# STM32.net
KiCad netlist of a schematic drawn in Altium Designer
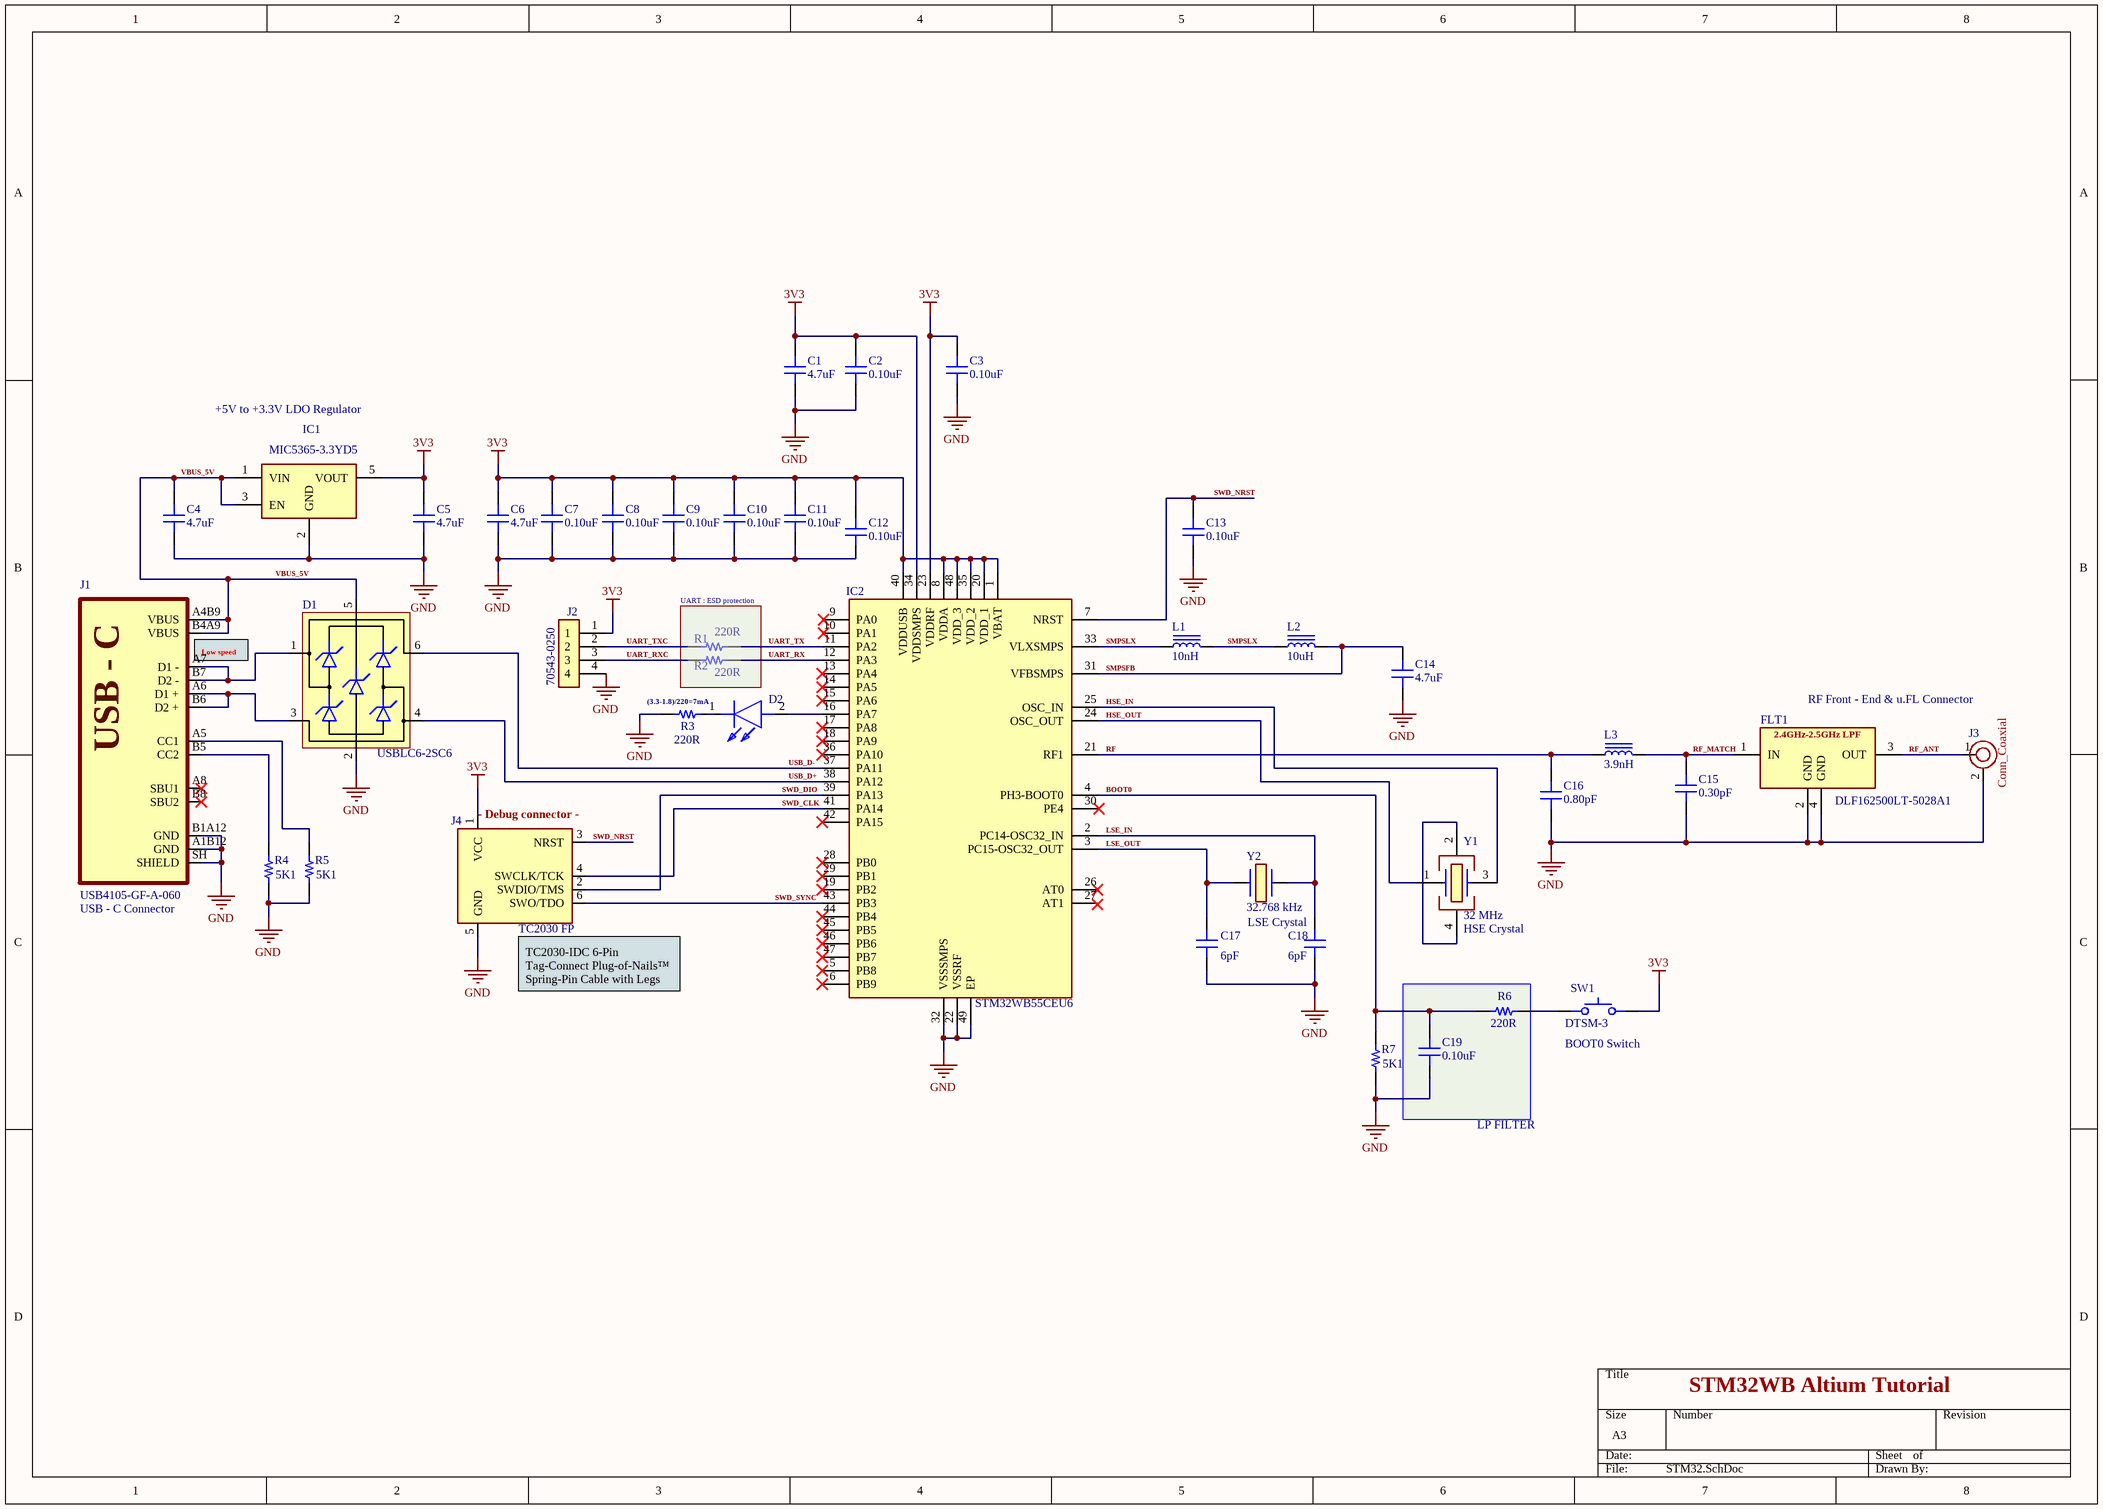
[diagram p0: STM32.SchDoc]

(export (version "E")
  (design (tool "Eeschema 10.0.6"))
  (components
    (comp (ref "C1")
      (value "4.7uF")
      (footprint "CAP 0805/2012")
      (description "CAP CER 4.7UF 10V X7R 0805")
      (fields
        (field (name "PART NUMBER") "CL21B475KPFNNNE")
        (field (name "MANUFACTURER") "Samsung Electro-Mechanics America, Inc.")
      )
      (libsource (lib "Capacitor - Ceramic - Sumsung") (part "CL21B475KPFNNNE"))
    )
    (comp (ref "C2")
      (value "0.10uF")
      (footprint "CAP 0402/1005")
      (description "CAP CER 0.1UF 16V X7R 0402")
      (fields
        (field (name "PART NUMBER") "CL05B104KO5NFNC")
        (field (name "MANUFACTURER") "Samsung Electro-Mechanics America, Inc.")
      )
      (libsource (lib "Capacitor - Ceramic - Sumsung") (part "CL05B104KO5NFNC"))
    )
    (comp (ref "C3")
      (value "0.10uF")
      (footprint "CAP 0402/1005")
      (description "CAP CER 0.1UF 16V X7R 0402")
      (fields
        (field (name "PART NUMBER") "CL05B104KO5NFNC")
        (field (name "MANUFACTURER") "Samsung Electro-Mechanics America, Inc.")
      )
      (libsource (lib "Capacitor - Ceramic - Sumsung") (part "CL05B104KO5NFNC"))
    )
    (comp (ref "C4")
      (value "4.7uF")
      (footprint "CAP 0805/2012")
      (description "CAP CER 4.7UF 10V X7R 0805")
      (fields
        (field (name "PART NUMBER") "CL21B475KPFNNNE")
        (field (name "MANUFACTURER") "Samsung Electro-Mechanics America, Inc.")
      )
      (libsource (lib "Capacitor - Ceramic - Sumsung") (part "CL21B475KPFNNNE"))
    )
    (comp (ref "C5")
      (value "4.7uF")
      (footprint "CAP 0805/2012")
      (description "CAP CER 4.7UF 10V X7R 0805")
      (fields
        (field (name "PART NUMBER") "CL21B475KPFNNNE")
        (field (name "MANUFACTURER") "Samsung Electro-Mechanics America, Inc.")
      )
      (libsource (lib "Capacitor - Ceramic - Sumsung") (part "CL21B475KPFNNNE"))
    )
    (comp (ref "C6")
      (value "4.7uF")
      (footprint "CAP 0805/2012")
      (description "CAP CER 4.7UF 10V X7R 0805")
      (fields
        (field (name "PART NUMBER") "CL21B475KPFNNNE")
        (field (name "MANUFACTURER") "Samsung Electro-Mechanics America, Inc.")
      )
      (libsource (lib "Capacitor - Ceramic - Sumsung") (part "CL21B475KPFNNNE"))
    )
    (comp (ref "C7")
      (value "0.10uF")
      (footprint "CAP 0402/1005")
      (description "CAP CER 0.1UF 16V X7R 0402")
      (fields
        (field (name "PART NUMBER") "CL05B104KO5NFNC")
        (field (name "MANUFACTURER") "Samsung Electro-Mechanics America, Inc.")
      )
      (libsource (lib "Capacitor - Ceramic - Sumsung") (part "CL05B104KO5NFNC"))
    )
    (comp (ref "C8")
      (value "0.10uF")
      (footprint "CAP 0402/1005")
      (description "CAP CER 0.1UF 16V X7R 0402")
      (fields
        (field (name "PART NUMBER") "CL05B104KO5NFNC")
        (field (name "MANUFACTURER") "Samsung Electro-Mechanics America, Inc.")
      )
      (libsource (lib "Capacitor - Ceramic - Sumsung") (part "CL05B104KO5NFNC"))
    )
    (comp (ref "C9")
      (value "0.10uF")
      (footprint "CAP 0402/1005")
      (description "CAP CER 0.1UF 16V X7R 0402")
      (fields
        (field (name "PART NUMBER") "CL05B104KO5NFNC")
        (field (name "MANUFACTURER") "Samsung Electro-Mechanics America, Inc.")
      )
      (libsource (lib "Capacitor - Ceramic - Sumsung") (part "CL05B104KO5NFNC"))
    )
    (comp (ref "C10")
      (value "0.10uF")
      (footprint "CAP 0402/1005")
      (description "CAP CER 0.1UF 16V X7R 0402")
      (fields
        (field (name "PART NUMBER") "CL05B104KO5NFNC")
        (field (name "MANUFACTURER") "Samsung Electro-Mechanics America, Inc.")
      )
      (libsource (lib "Capacitor - Ceramic - Sumsung") (part "CL05B104KO5NFNC"))
    )
    (comp (ref "C11")
      (value "0.10uF")
      (footprint "CAP 0402/1005")
      (description "CAP CER 0.1UF 16V X7R 0402")
      (fields
        (field (name "PART NUMBER") "CL05B104KO5NFNC")
        (field (name "MANUFACTURER") "Samsung Electro-Mechanics America, Inc.")
      )
      (libsource (lib "Capacitor - Ceramic - Sumsung") (part "CL05B104KO5NFNC"))
    )
    (comp (ref "C12")
      (value "0.10uF")
      (footprint "CAP 0402/1005")
      (description "CAP CER 0.1UF 16V X7R 0402")
      (fields
        (field (name "PART NUMBER") "CL05B104KO5NFNC")
        (field (name "MANUFACTURER") "Samsung Electro-Mechanics America, Inc.")
      )
      (libsource (lib "Capacitor - Ceramic - Sumsung") (part "CL05B104KO5NFNC"))
    )
    (comp (ref "C13")
      (value "0.10uF")
      (footprint "CAP 0402/1005")
      (description "CAP CER 0.1UF 16V X7R 0402")
      (fields
        (field (name "PART NUMBER") "CL05B104KO5NFNC")
        (field (name "MANUFACTURER") "Samsung Electro-Mechanics America, Inc.")
      )
      (libsource (lib "Capacitor - Ceramic - Sumsung") (part "CL05B104KO5NFNC"))
    )
    (comp (ref "C14")
      (value "4.7uF")
      (footprint "CAP 0805/2012")
      (description "CAP CER 4.7UF 10V X7R 0805")
      (fields
        (field (name "PART NUMBER") "CL21B475KPFNNNE")
        (field (name "MANUFACTURER") "Samsung Electro-Mechanics America, Inc.")
      )
      (libsource (lib "Capacitor - Ceramic - Sumsung") (part "CL21B475KPFNNNE"))
    )
    (comp (ref "C15")
      (value "0.30pF")
      (footprint "CAP 0201/0603 RF")
      (description "CAP CER 0.3PF 25V NP0 0201")
      (fields
        (field (name "PART NUMBER") "250R05L0R3BV4T")
        (field (name "MANUFACTURER") "Johanson Technology Inc.")
      )
      (libsource (lib "Capacitor - RF") (part "250R05L0R3BV4T"))
    )
    (comp (ref "C16")
      (value "0.80pF")
      (footprint "CAP 0402/1005 RF")
      (description "CAP CER 0.80PF 50V NP0 0402")
      (fields
        (field (name "PART NUMBER") "GJM1555C1HR80BB01D")
        (field (name "MANUFACTURER") "Murata Electronics North America")
      )
      (libsource (lib "Capacitor - RF") (part "GJM1555C1HR80BB01D"))
    )
    (comp (ref "C17")
      (value "6pF")
      (footprint "CAP 0201/0603")
      (description "CAP CER 6PF 25V NP0 0201")
      (fields
        (field (name "PART NUMBER") "CL03C060BA3GNNC")
        (field (name "MANUFACTURER") "Samsung Electro-Mechanics America, Inc.")
      )
      (libsource (lib "Capacitor - Ceramic - Sumsung") (part "CL03C060BA3GNNC"))
    )
    (comp (ref "C18")
      (value "6pF")
      (footprint "CAP 0201/0603")
      (description "CAP CER 6PF 25V NP0 0201")
      (fields
        (field (name "PART NUMBER") "CL03C060BA3GNNC")
        (field (name "MANUFACTURER") "Samsung Electro-Mechanics America, Inc.")
      )
      (libsource (lib "Capacitor - Ceramic - Sumsung") (part "CL03C060BA3GNNC"))
    )
    (comp (ref "C19")
      (value "0.10uF")
      (footprint "CAP 0402/1005")
      (description "CAP CER 0.1UF 16V X7R 0402")
      (fields
        (field (name "PART NUMBER") "CL05B104KO5NFNC")
        (field (name "MANUFACTURER") "Samsung Electro-Mechanics America, Inc.")
      )
      (libsource (lib "Capacitor - Ceramic - Sumsung") (part "CL05B104KO5NFNC"))
    )
    (comp (ref "D1")
      (value "USBLC6-2SC6")
      (footprint "SOT-23-6")
      (description "Low-Capacitance ESD Protection USB")
      (fields (field (name "MANUFACTURER") "STMicroelectronics"))
      (libsource (lib "Own_Library") (part "USBLC6-2SC6"))
    )
    (comp (ref "D2")
      (value "150060GS55040")
      (footprint "LEDC1608X50N")
      (description "LED SMD 0603 Green 520nm")
      (fields (field (name "MOUSER PART NUMBER") "710-150060GS55040"))
      (libsource (lib "Own_Library") (part "150060GS55040"))
    )
    (comp (ref "FLT1")
      (value "DLF162500LT-5028A1")
      (footprint "DLF162500LT5028A1")
      (description "LTCC Low Pass filter 2400-2500MHz")
      (fields (field (name "MOUSER PART NUMBER") "810-DLF16250LT5028A1"))
      (libsource (lib "Own_Library") (part "DLF162500LT-5028A1"))
    )
    (comp (ref "IC1")
      (value "MIC5365-3.3YD5")
      (footprint "SOT95P280X100-5N")
      (description "Integrated Circuit")
      (fields
        (field (name "MANUFACTURER_PART_NUMBER") "MIC5365-3.3YD5-TR")
        (field (name "MOUSER PART NUMBER") "998-MIC5365-3.3YD5TR")
      )
      (libsource (lib "Own_Library") (part "MIC5365-3.3YD5-TR"))
    )
    (comp (ref "IC2")
      (value "STM32WB55CEU6")
      (footprint "QFN50P700X700X65-49N-D")
      (fields (field (name "MOUSER PART NUMBER") "511-STM32WB55CEU6"))
      (libsource (lib "sch_lib_own_") (part "STM32WB55CEU6"))
    )
    (comp (ref "J1")
      (value "USB4105-GF-A-060")
      (footprint "USB4105-GF-A-060")
      (description "USB Connector Type C SMT 12 Pin")
      (fields (field (name "MANUFACTURER") "GCT"))
      (libsource (lib "Own_Library") (part "USB4105-GF-A-060"))
    )
    (comp (ref "J2")
      (value "70543-0250")
      (footprint "705430250")
      (description "Connector 1X4 Headers & Wire Housings")
      (fields (field (name "MOUSER PART NUMBER") "538-70543-0250"))
      (libsource (lib "sch_lib_own_") (part "70543-0250"))
    )
    (comp (ref "J3")
      (value "Conn_Coaxial")
      (footprint "CON-SMA-EDGE-S")
      (description "RF Connector SMA Female 50 Ohms 18 GHz PCB Edge Mount")
      (fields
        (field (name "MANUFACTURER") "RF Solutions")
        (field (name "MANUFACTURER PART NUMBER") "CON-SMA-EDGE-S")
      )
      (libsource (lib "Own_Library") (part "CON-SMA-EDGE-S"))
    )
    (comp (ref "J4")
      (value "TC2030 FP")
      (footprint "TC2030-FP")
      (description "Tag-Connect No-Solder SWD Debug Connector DO NOT PLACE")
      (fields (field (name "MANUFACTURER") "Tag-Connect") (field (name "MANUFACTURER PART NUMBER") "TC2030"))
      (libsource (lib "Own_Library") (part "TC2030"))
    )
    (comp (ref "L1")
      (value "10nH")
      (footprint "IND 0402/1005 RF WW")
      (description "FIXED IND 10NH 500MA 170 MOHM")
      (fields
        (field (name "PART NUMBER") "LQW15AN10NJ00D")
        (field (name "MANUFACTURER") "Murata Electronics North America")
      )
      (libsource (lib "Inductor - RF") (part "LQW15AN10NJ00D"))
    )
    (comp (ref "L2")
      (value "10uH")
      (footprint "TDK VLS252012HBX-1")
      (description "FIXED IND 10UH 1A 540 MOHM SMD")
      (fields
        (field (name "PART NUMBER") "VLS252012HBX-100M-1")
        (field (name "MANUFACTURER") "TDK Corporation")
      )
      (libsource (lib "Inductor - Power") (part "VLS252012HBX-100M-1"))
    )
    (comp (ref "L3")
      (value "3.9nH")
      (footprint "LQG15WH0N7B02D")
      (description "FIXED IND 2.7NH 800MA 0.15OHM SM")
      (fields
        (field (name "PART NUMBER") "LQW15AN3N9D10D")
        (field (name "MANUFACTURER") "Murata Electronics North America")
      )
      (libsource (lib "Own_Library") (part "LQG15HS2N7S02D"))
    )
    (comp (ref "R1")
      (value "220R")
      (footprint "RES 0603/1608")
      (description "RES SMD 220R OHM 5% 1/8W 0603")
      (fields (field (name "PART NUMBER") "0603S8J0221") (field (name "MANUFACTURER") "Uniohm"))
      (libsource (lib "Resistor - Chip - Uniohm") (part "0603S8J0221"))
    )
    (comp (ref "R2")
      (value "220R")
      (footprint "RES 0603/1608")
      (description "RES SMD 220R OHM 5% 1/8W 0603")
      (fields (field (name "PART NUMBER") "0603S8J0221") (field (name "MANUFACTURER") "Uniohm"))
      (libsource (lib "Resistor - Chip - Uniohm") (part "0603S8J0221"))
    )
    (comp (ref "R3")
      (value "220R")
      (footprint "RES 0603/1608")
      (description "RES SMD 220R OHM 5% 1/8W 0603")
      (fields (field (name "PART NUMBER") "0603S8J0221") (field (name "MANUFACTURER") "Uniohm"))
      (libsource (lib "Resistor - Chip - Uniohm") (part "0603S8J0221"))
    )
    (comp (ref "R4")
      (value "5K1")
      (footprint "RES 0603/1608")
      (description "RES SMD 5K1 OHM 5% 1/8W 0603")
      (fields (field (name "PART NUMBER") "0603S8J0512") (field (name "MANUFACTURER") "Uniohm"))
      (libsource (lib "Resistor - Chip - Uniohm") (part "0603S8J0512"))
    )
    (comp (ref "R5")
      (value "5K1")
      (footprint "RES 0603/1608")
      (description "RES SMD 5K1 OHM 5% 1/8W 0603")
      (fields (field (name "PART NUMBER") "0603S8J0512") (field (name "MANUFACTURER") "Uniohm"))
      (libsource (lib "Resistor - Chip - Uniohm") (part "0603S8J0512"))
    )
    (comp (ref "R6")
      (value "220R")
      (footprint "RES 0603/1608")
      (description "RES SMD 220R OHM 5% 1/8W 0603")
      (fields (field (name "PART NUMBER") "0603S8J0221") (field (name "MANUFACTURER") "Uniohm"))
      (libsource (lib "Resistor - Chip - Uniohm") (part "0603S8J0221"))
    )
    (comp (ref "R7")
      (value "5K1")
      (footprint "RES 0603/1608")
      (description "RES SMD 5K1 OHM 5% 1/8W 0603")
      (fields (field (name "PART NUMBER") "0603S8J0512") (field (name "MANUFACTURER") "Uniohm"))
      (libsource (lib "Resistor - Chip - Uniohm") (part "0603S8J0512"))
    )
    (comp (ref "SW1")
      (value "DTSM-3")
      (footprint "DTSM-3")
      (description "Tactile Switch SMD SPST")
      (fields (field (name "MANUFACTURER") "Diptronics"))
      (libsource (lib "Own_Library") (part "DTSM-3"))
    )
    (comp (ref "Y1")
      (value "32 MHz")
      (footprint "7B32000MAAJT")
      (description "Crystals 32.000MHz 30ppm -20 +70C 18pF Crystal Oscillator")
      (fields
        (field (name "MANUFACTURER_PART_NUMBER") "7B-16.000MAAJ-T")
        (field (name "MOUSER PART NUMBER") "717-7B-16.000MAAJ-T")
      )
      (libsource (lib "sch_lib_own_") (part "7B-32.000MAAJ-T"))
    )
    (comp (ref "Y2")
      (value "32.768 kHz")
      (footprint "ABM3")
      (description "Crystal Oscillator 32.768 kHz ±10ppm 6pF 50 KOhms Crystal or Oscillator")
      (fields (field (name "MANUFACTURER_PART_NUMBER") "ABM316000MHZB2T"))
      (libsource (lib "sch_lib_own_") (part "ABS07-32.768KHZ-6-T"))
    )
  )
  (nets
    (net (code "1") (name "/BOOT0") (class "Default")
      (node (ref "C19") (pin "2") (pinfunction "2_2") (pintype "passive"))
      (node (ref "IC2") (pin "4") (pinfunction "PH3-BOOT0_4") (pintype "passive"))
      (node (ref "R6") (pin "1") (pinfunction "1_1") (pintype "passive"))
      (node (ref "R7") (pin "2") (pinfunction "2_2") (pintype "passive"))
    )
    (net (code "2") (name "/HSE_IN") (class "Default")
      (node (ref "IC2") (pin "25") (pinfunction "OSC_IN_25") (pintype "passive"))
      (node (ref "Y1") (pin "3") (pinfunction "CRYSTAL_2_3") (pintype "passive"))
    )
    (net (code "3") (name "/HSE_OUT") (class "Default")
      (node (ref "IC2") (pin "24") (pinfunction "OSC_OUT_24") (pintype "passive"))
      (node (ref "Y1") (pin "1") (pinfunction "CRYSTAL_1_1") (pintype "passive"))
    )
    (net (code "4") (name "/LSE_IN") (class "Default")
      (node (ref "C18") (pin "1") (pinfunction "1_1") (pintype "passive"))
      (node (ref "IC2") (pin "2") (pinfunction "PC14-OSC32_IN_2") (pintype "passive"))
      (node (ref "Y2") (pin "2") (pinfunction "2_2") (pintype "passive"))
    )
    (net (code "5") (name "/LSE_OUT") (class "Default")
      (node (ref "C17") (pin "2") (pinfunction "2_2") (pintype "passive"))
      (node (ref "IC2") (pin "3") (pinfunction "PC15-OSC32_OUT_3") (pintype "passive"))
      (node (ref "Y2") (pin "1") (pinfunction "1_1") (pintype "passive"))
    )
    (net (code "6") (name "/RF") (class "Default")
      (node (ref "C16") (pin "2") (pinfunction "2_2") (pintype "passive"))
      (node (ref "IC2") (pin "21") (pinfunction "RF1_21") (pintype "passive"))
      (node (ref "L3") (pin "1") (pinfunction "1_1") (pintype "passive"))
    )
    (net (code "7") (name "/RF_ANT") (class "Default")
      (node (ref "FLT1") (pin "3") (pinfunction "OUT_3") (pintype "passive"))
      (node (ref "J3") (pin "1") (pinfunction "1_1") (pintype "passive"))
    )
    (net (code "8") (name "/RF_MATCH") (class "Default")
      (node (ref "C15") (pin "2") (pinfunction "2_2") (pintype "passive"))
      (node (ref "FLT1") (pin "1") (pinfunction "IN_1") (pintype "passive"))
      (node (ref "L3") (pin "2") (pinfunction "2_2") (pintype "passive"))
    )
    (net (code "9") (name "/SMPSFB") (class "Default")
      (node (ref "C14") (pin "2") (pinfunction "2_2") (pintype "passive"))
      (node (ref "IC2") (pin "31") (pinfunction "VFBSMPS_31") (pintype "passive"))
      (node (ref "L2") (pin "2") (pinfunction "2_2") (pintype "passive"))
    )
    (net (code "10") (name "/SMPSLX") (class "Default")
      (node (ref "IC2") (pin "33") (pinfunction "VLXSMPS_33") (pintype "passive"))
      (node (ref "L1") (pin "1") (pinfunction "1_1") (pintype "passive"))
      (node (ref "L1") (pin "2") (pinfunction "2_2") (pintype "passive"))
      (node (ref "L2") (pin "1") (pinfunction "1_1") (pintype "passive"))
    )
    (net (code "11") (name "/SWD_CLK") (class "Default")
      (node (ref "IC2") (pin "41") (pinfunction "PA14_41") (pintype "passive"))
      (node (ref "J4") (pin "4") (pinfunction "SWCLK/TCK_4") (pintype "passive"))
    )
    (net (code "12") (name "/SWD_DIO") (class "Default")
      (node (ref "IC2") (pin "39") (pinfunction "PA13_39") (pintype "passive"))
      (node (ref "J4") (pin "2") (pinfunction "SWDIO/TMS_2") (pintype "passive"))
    )
    (net (code "13") (name "/SWD_NRST") (class "Default")
      (node (ref "C13") (pin "2") (pinfunction "2_2") (pintype "passive"))
      (node (ref "IC2") (pin "7") (pinfunction "NRST_7") (pintype "passive"))
      (node (ref "J4") (pin "3") (pinfunction "NRST_3") (pintype "passive"))
    )
    (net (code "14") (name "/SWD_SYNC") (class "Default")
      (node (ref "IC2") (pin "43") (pinfunction "PB3_43") (pintype "passive"))
      (node (ref "J4") (pin "6") (pinfunction "SWO/TDO_6") (pintype "passive"))
    )
    (net (code "15") (name "/UART_RX") (class "Default")
      (node (ref "IC2") (pin "12") (pinfunction "PA3_12") (pintype "passive"))
      (node (ref "R2") (pin "2") (pinfunction "2_2") (pintype "passive"))
    )
    (net (code "16") (name "/UART_RXC") (class "Default")
      (node (ref "J2") (pin "3") (pinfunction "3_3") (pintype "passive"))
      (node (ref "R2") (pin "1") (pinfunction "1_1") (pintype "passive"))
    )
    (net (code "17") (name "/UART_TX") (class "Default")
      (node (ref "IC2") (pin "11") (pinfunction "PA2_11") (pintype "passive"))
      (node (ref "R1") (pin "2") (pinfunction "2_2") (pintype "passive"))
    )
    (net (code "18") (name "/UART_TXC") (class "Default")
      (node (ref "J2") (pin "2") (pinfunction "2_2") (pintype "passive"))
      (node (ref "R1") (pin "1") (pinfunction "1_1") (pintype "passive"))
    )
    (net (code "19") (name "/USB_D+") (class "Default")
      (node (ref "D1") (pin "4") (pinfunction "IO2_4") (pintype "bidirectional"))
      (node (ref "IC2") (pin "38") (pinfunction "PA12_38") (pintype "passive"))
    )
    (net (code "20") (name "/USB_D-") (class "Default")
      (node (ref "D1") (pin "6") (pinfunction "IO1_6") (pintype "bidirectional"))
      (node (ref "IC2") (pin "37") (pinfunction "PA11_37") (pintype "passive"))
    )
    (net (code "21") (name "/VBUS_5V") (class "Default")
      (node (ref "C4") (pin "2") (pinfunction "2_2") (pintype "passive"))
      (node (ref "D1") (pin "5") (pinfunction "VBUS_5") (pintype "power_in"))
      (node (ref "IC1") (pin "1") (pinfunction "VIN_1") (pintype "passive"))
      (node (ref "IC1") (pin "3") (pinfunction "EN_3") (pintype "passive"))
      (node (ref "J1") (pin "A4B9") (pinfunction "VBUS_A4B9") (pintype "passive"))
      (node (ref "J1") (pin "B4A9") (pinfunction "VBUS_B4A9") (pintype "passive"))
    )
    (net (code "22") (name "3V3") (class "Default")
      (node (ref "C1") (pin "2") (pinfunction "2_2") (pintype "passive"))
      (node (ref "C10") (pin "2") (pinfunction "2_2") (pintype "passive"))
      (node (ref "C11") (pin "2") (pinfunction "2_2") (pintype "passive"))
      (node (ref "C12") (pin "2") (pinfunction "2_2") (pintype "passive"))
      (node (ref "C2") (pin "2") (pinfunction "2_2") (pintype "passive"))
      (node (ref "C3") (pin "2") (pinfunction "2_2") (pintype "passive"))
      (node (ref "C5") (pin "2") (pinfunction "2_2") (pintype "passive"))
      (node (ref "C6") (pin "2") (pinfunction "2_2") (pintype "passive"))
      (node (ref "C7") (pin "2") (pinfunction "2_2") (pintype "passive"))
      (node (ref "C8") (pin "2") (pinfunction "2_2") (pintype "passive"))
      (node (ref "C9") (pin "2") (pinfunction "2_2") (pintype "passive"))
      (node (ref "IC1") (pin "5") (pinfunction "VOUT_5") (pintype "passive"))
      (node (ref "IC2") (pin "1") (pinfunction "VBAT_1") (pintype "passive"))
      (node (ref "IC2") (pin "20") (pinfunction "VDD_1_20") (pintype "passive"))
      (node (ref "IC2") (pin "23") (pinfunction "VDDRF_23") (pintype "passive"))
      (node (ref "IC2") (pin "34") (pinfunction "VDDSMPS_34") (pintype "passive"))
      (node (ref "IC2") (pin "35") (pinfunction "VDD_2_35") (pintype "passive"))
      (node (ref "IC2") (pin "40") (pinfunction "VDDUSB_40") (pintype "passive"))
      (node (ref "IC2") (pin "48") (pinfunction "VDD_3_48") (pintype "passive"))
      (node (ref "IC2") (pin "8") (pinfunction "VDDA_8") (pintype "passive"))
      (node (ref "J2") (pin "1") (pinfunction "1_1") (pintype "passive"))
      (node (ref "J4") (pin "1") (pinfunction "VCC_1") (pintype "passive"))
      (node (ref "SW1") (pin "2") (pintype "passive"))
    )
    (net (code "23") (name "GND") (class "Default")
      (node (ref "C1") (pin "1") (pinfunction "1_1") (pintype "passive"))
      (node (ref "C10") (pin "1") (pinfunction "1_1") (pintype "passive"))
      (node (ref "C11") (pin "1") (pinfunction "1_1") (pintype "passive"))
      (node (ref "C12") (pin "1") (pinfunction "1_1") (pintype "passive"))
      (node (ref "C13") (pin "1") (pinfunction "1_1") (pintype "passive"))
      (node (ref "C14") (pin "1") (pinfunction "1_1") (pintype "passive"))
      (node (ref "C15") (pin "1") (pinfunction "1_1") (pintype "passive"))
      (node (ref "C16") (pin "1") (pinfunction "1_1") (pintype "passive"))
      (node (ref "C17") (pin "1") (pinfunction "1_1") (pintype "passive"))
      (node (ref "C18") (pin "2") (pinfunction "2_2") (pintype "passive"))
      (node (ref "C19") (pin "1") (pinfunction "1_1") (pintype "passive"))
      (node (ref "C2") (pin "1") (pinfunction "1_1") (pintype "passive"))
      (node (ref "C3") (pin "1") (pinfunction "1_1") (pintype "passive"))
      (node (ref "C4") (pin "1") (pinfunction "1_1") (pintype "passive"))
      (node (ref "C5") (pin "1") (pinfunction "1_1") (pintype "passive"))
      (node (ref "C6") (pin "1") (pinfunction "1_1") (pintype "passive"))
      (node (ref "C7") (pin "1") (pinfunction "1_1") (pintype "passive"))
      (node (ref "C8") (pin "1") (pinfunction "1_1") (pintype "passive"))
      (node (ref "C9") (pin "1") (pinfunction "1_1") (pintype "passive"))
      (node (ref "D1") (pin "2") (pinfunction "GND_2") (pintype "power_in"))
      (node (ref "FLT1") (pin "2") (pinfunction "GND_2") (pintype "passive"))
      (node (ref "FLT1") (pin "4") (pinfunction "GND_4") (pintype "passive"))
      (node (ref "IC1") (pin "2") (pinfunction "GND_2") (pintype "passive"))
      (node (ref "IC2") (pin "22") (pinfunction "VSSRF_22") (pintype "passive"))
      (node (ref "IC2") (pin "32") (pinfunction "VSSSMPS_32") (pintype "passive"))
      (node (ref "IC2") (pin "49") (pinfunction "EP_49") (pintype "passive"))
      (node (ref "J1") (pin "A1B12") (pinfunction "GND_A1B12") (pintype "passive"))
      (node (ref "J1") (pin "B1A12") (pinfunction "GND_B1A12") (pintype "passive"))
      (node (ref "J1") (pin "SH") (pinfunction "SHIELD_SH") (pintype "passive"))
      (node (ref "J2") (pin "4") (pinfunction "4_4") (pintype "passive"))
      (node (ref "J3") (pin "2") (pinfunction "2_2") (pintype "passive"))
      (node (ref "J4") (pin "5") (pinfunction "GND_5") (pintype "passive"))
      (node (ref "R3") (pin "1") (pinfunction "1_1") (pintype "passive"))
      (node (ref "R4") (pin "1") (pinfunction "1_1") (pintype "passive"))
      (node (ref "R5") (pin "1") (pinfunction "1_1") (pintype "passive"))
      (node (ref "R7") (pin "1") (pinfunction "1_1") (pintype "passive"))
    )
    (net (code "24") (name "Net-(D2-A)") (class "Default")
      (node (ref "D2") (pin "2") (pinfunction "A_2") (pintype "passive"))
      (node (ref "IC2") (pin "16") (pinfunction "PA7_16") (pintype "passive"))
    )
    (net (code "25") (name "Net-(D2-K)") (class "Default")
      (node (ref "D2") (pin "1") (pinfunction "K_1") (pintype "passive"))
      (node (ref "R3") (pin "2") (pinfunction "2_2") (pintype "passive"))
    )
    (net (code "26") (name "Net-(J1-CC1)") (class "Default")
      (node (ref "J1") (pin "A5") (pinfunction "CC1_A5") (pintype "passive"))
      (node (ref "R5") (pin "2") (pinfunction "2_2") (pintype "passive"))
    )
    (net (code "27") (name "Net-(J1-CC2)") (class "Default")
      (node (ref "J1") (pin "B5") (pinfunction "CC2_B5") (pintype "passive"))
      (node (ref "R4") (pin "2") (pinfunction "2_2") (pintype "passive"))
    )
    (net (code "28") (name "Net-(J1-D1_+)") (class "Default")
      (node (ref "D1") (pin "3") (pinfunction "IO2_3") (pintype "bidirectional"))
      (node (ref "J1") (pin "A6") (pinfunction "D1_+_A6") (pintype "passive"))
      (node (ref "J1") (pin "B6") (pinfunction "D2_+_B6") (pintype "passive"))
    )
    (net (code "29") (name "Net-(J1-D1_-)") (class "Default")
      (node (ref "D1") (pin "1") (pinfunction "IO1_1") (pintype "bidirectional"))
      (node (ref "J1") (pin "A7") (pinfunction "D1_-_A7") (pintype "passive"))
      (node (ref "J1") (pin "B7") (pinfunction "D2_-_B7") (pintype "passive"))
    )
    (net (code "30") (name "Net-(R6-Pad2)") (class "Default")
      (node (ref "R6") (pin "2") (pinfunction "2_2") (pintype "passive"))
      (node (ref "SW1") (pin "1") (pintype "passive"))
    )
    (net (code "31") (name "Net-(Y1-GND_1)") (class "Default")
      (node (ref "Y1") (pin "2") (pinfunction "GND_1_2") (pintype "passive"))
      (node (ref "Y1") (pin "4") (pinfunction "GND_2_4") (pintype "passive"))
    )
    (net (code "32") (name "unconnected-(IC2-AT0-Pad26)") (class "Default")
      (node (ref "IC2") (pin "26") (pinfunction "AT0_26") (pintype "passive"))
    )
    (net (code "33") (name "unconnected-(IC2-AT1-Pad27)") (class "Default")
      (node (ref "IC2") (pin "27") (pinfunction "AT1_27") (pintype "passive"))
    )
    (net (code "34") (name "unconnected-(IC2-PA0-Pad9)") (class "Default")
      (node (ref "IC2") (pin "9") (pinfunction "PA0_9") (pintype "passive"))
    )
    (net (code "35") (name "unconnected-(IC2-PA1-Pad10)") (class "Default")
      (node (ref "IC2") (pin "10") (pinfunction "PA1_10") (pintype "passive"))
    )
    (net (code "36") (name "unconnected-(IC2-PA4-Pad13)") (class "Default")
      (node (ref "IC2") (pin "13") (pinfunction "PA4_13") (pintype "passive+no_connect"))
    )
    (net (code "37") (name "unconnected-(IC2-PA5-Pad14)") (class "Default")
      (node (ref "IC2") (pin "14") (pinfunction "PA5_14") (pintype "passive+no_connect"))
    )
    (net (code "38") (name "unconnected-(IC2-PA6-Pad15)") (class "Default")
      (node (ref "IC2") (pin "15") (pinfunction "PA6_15") (pintype "passive+no_connect"))
    )
    (net (code "39") (name "unconnected-(IC2-PA8-Pad17)") (class "Default")
      (node (ref "IC2") (pin "17") (pinfunction "PA8_17") (pintype "power_in+no_connect"))
    )
    (net (code "40") (name "unconnected-(IC2-PA9-Pad18)") (class "Default")
      (node (ref "IC2") (pin "18") (pinfunction "PA9_18") (pintype "passive+no_connect"))
    )
    (net (code "41") (name "unconnected-(IC2-PA10-Pad36)") (class "Default")
      (node (ref "IC2") (pin "36") (pinfunction "PA10_36") (pintype "passive+no_connect"))
    )
    (net (code "42") (name "unconnected-(IC2-PA15-Pad42)") (class "Default")
      (node (ref "IC2") (pin "42") (pinfunction "PA15_42") (pintype "passive+no_connect"))
    )
    (net (code "43") (name "unconnected-(IC2-PB0-Pad28)") (class "Default")
      (node (ref "IC2") (pin "28") (pinfunction "PB0_28") (pintype "passive+no_connect"))
    )
    (net (code "44") (name "unconnected-(IC2-PB1-Pad29)") (class "Default")
      (node (ref "IC2") (pin "29") (pinfunction "PB1_29") (pintype "passive+no_connect"))
    )
    (net (code "45") (name "unconnected-(IC2-PB2-Pad19)") (class "Default")
      (node (ref "IC2") (pin "19") (pinfunction "PB2_19") (pintype "passive+no_connect"))
    )
    (net (code "46") (name "unconnected-(IC2-PB4-Pad44)") (class "Default")
      (node (ref "IC2") (pin "44") (pinfunction "PB4_44") (pintype "passive+no_connect"))
    )
    (net (code "47") (name "unconnected-(IC2-PB5-Pad45)") (class "Default")
      (node (ref "IC2") (pin "45") (pinfunction "PB5_45") (pintype "passive+no_connect"))
    )
    (net (code "48") (name "unconnected-(IC2-PB6-Pad46)") (class "Default")
      (node (ref "IC2") (pin "46") (pinfunction "PB6_46") (pintype "passive+no_connect"))
    )
    (net (code "49") (name "unconnected-(IC2-PB7-Pad47)") (class "Default")
      (node (ref "IC2") (pin "47") (pinfunction "PB7_47") (pintype "passive+no_connect"))
    )
    (net (code "50") (name "unconnected-(IC2-PB8-Pad5)") (class "Default")
      (node (ref "IC2") (pin "5") (pinfunction "PB8_5") (pintype "passive+no_connect"))
    )
    (net (code "51") (name "unconnected-(IC2-PB9-Pad6)") (class "Default")
      (node (ref "IC2") (pin "6") (pinfunction "PB9_6") (pintype "passive+no_connect"))
    )
    (net (code "52") (name "unconnected-(IC2-PE4-Pad30)") (class "Default")
      (node (ref "IC2") (pin "30") (pinfunction "PE4_30") (pintype "passive+no_connect"))
    )
    (net (code "53") (name "unconnected-(J1-SBU1-PadA8)") (class "Default")
      (node (ref "J1") (pin "A8") (pinfunction "SBU1_A8") (pintype "passive+no_connect"))
    )
    (net (code "54") (name "unconnected-(J1-SBU2-PadB8)") (class "Default")
      (node (ref "J1") (pin "B8") (pinfunction "SBU2_B8") (pintype "passive+no_connect"))
    )
  )
)
